# Nine-axis_Gyroscope_Module.net
KiCad netlist of a schematic drawn in Altium Designer
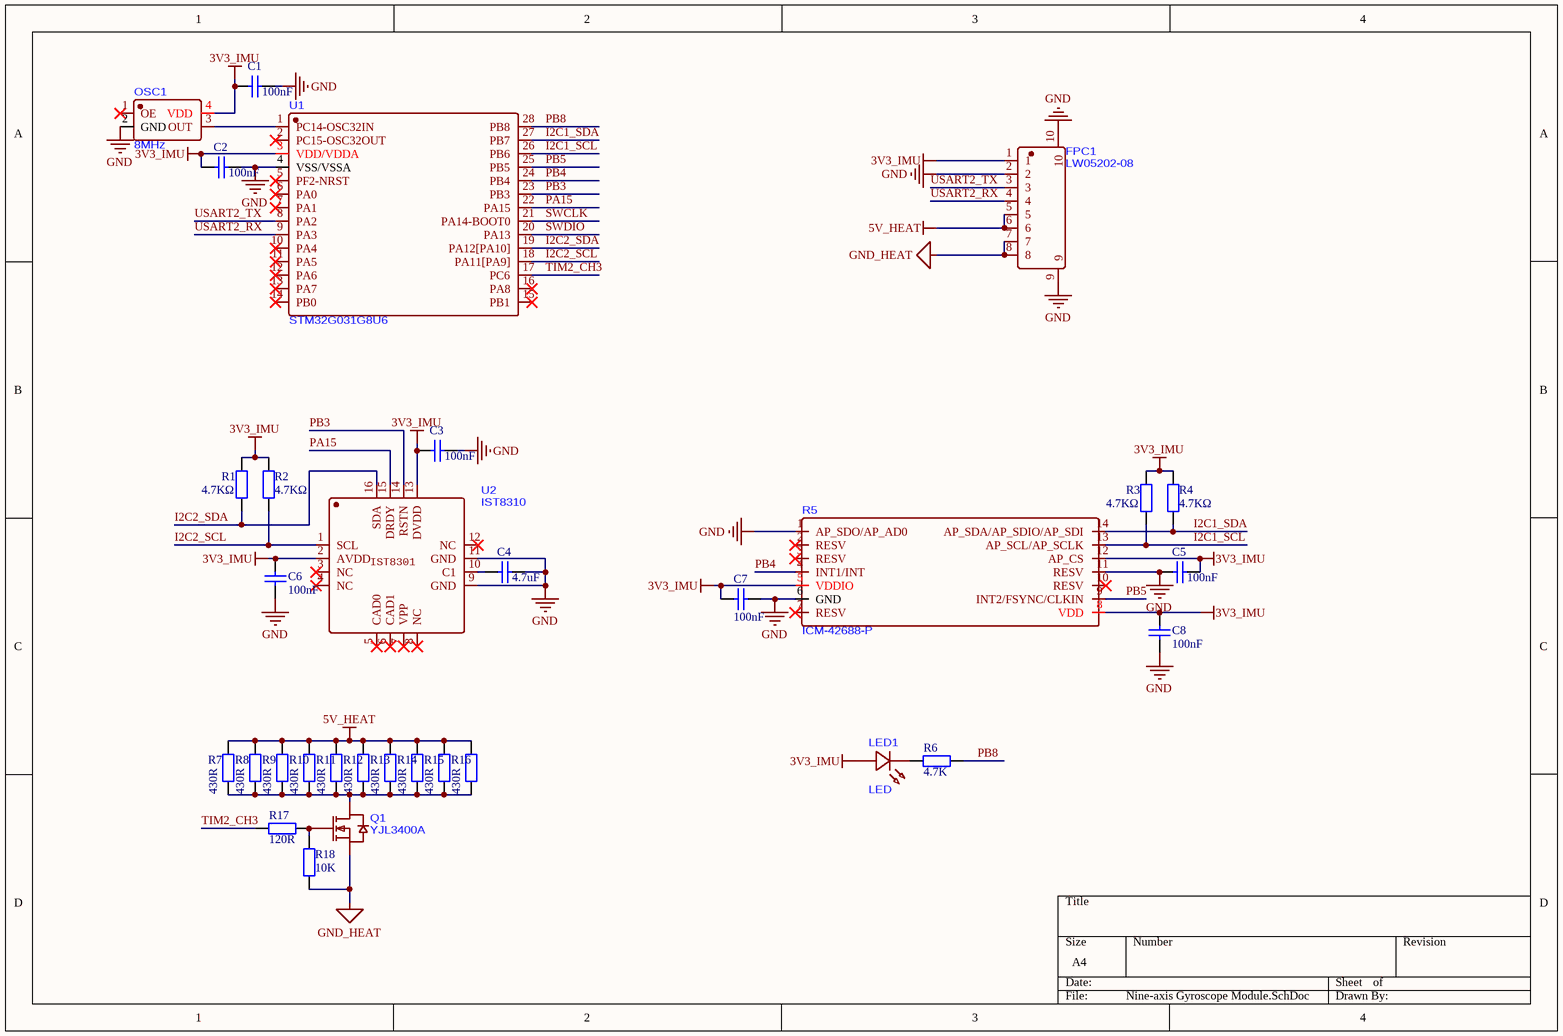
[diagram p0: Nine-axis Gyroscope Module.SchDoc]

(export (version "E")
  (design (tool "Eeschema 10.0.6"))
  (components
    (comp (ref "C1")
      (value "100nF")
      (footprint "0402_C")
      (description "贴片电容")
      (libsource (lib "Miscellaneous Devices LC") (part "0402 100nF (104) 10% 16V"))
    )
    (comp (ref "C2")
      (value "100nF")
      (footprint "0402_C")
      (description "贴片电容")
      (libsource (lib "Miscellaneous Devices LC") (part "0402 100nF (104) 10% 16V"))
    )
    (comp (ref "C3")
      (value "100nF")
      (footprint "0402_C")
      (description "贴片电容")
      (libsource (lib "Miscellaneous Devices LC") (part "0402 100nF (104) 10% 16V"))
    )
    (comp (ref "C4")
      (value "4.7uF")
      (footprint "0402_C")
      (description "贴片电容")
      (libsource (lib "Miscellaneous Devices LC") (part "0402 4.7uF (475) 20% 10V"))
    )
    (comp (ref "C5")
      (value "100nF")
      (footprint "0402_C")
      (description "贴片电容")
      (libsource (lib "Miscellaneous Devices LC") (part "0402 100nF (104) 10% 16V"))
    )
    (comp (ref "C6")
      (value "100nF")
      (footprint "0402_C")
      (description "贴片电容")
      (libsource (lib "Miscellaneous Devices LC") (part "0402 100nF (104) 10% 16V"))
    )
    (comp (ref "C7")
      (value "100nF")
      (footprint "0402_C")
      (description "贴片电容")
      (libsource (lib "Miscellaneous Devices LC") (part "0402 100nF (104) 10% 16V"))
    )
    (comp (ref "C8")
      (value "100nF")
      (footprint "0402_C")
      (description "贴片电容")
      (libsource (lib "Miscellaneous Devices LC") (part "0402 100nF (104) 10% 16V"))
    )
    (comp (ref "FPC1")
      (value "LW05202-08")
      (footprint "FPC-SMD_8P-P0.50_LW05202-08")
      (libsource (lib "VeryNB_H750") (part "LW05202-08"))
    )
    (comp (ref "LED1")
      (value "LED")
      (footprint "LED0402-RD")
      (libsource (lib "VeryNB_H750") (part "TJ-S1005CL4T5ALC3DW-A5"))
    )
    (comp (ref "OSC1")
      (value "8MHz")
      (footprint "OSC-SMD_4P-L2.0-W1.6-BL_ABRACON_AMPMAXXX")
      (libsource (lib "VeryNB_H750") (part "AMPMAFC-25.0000T"))
    )
    (comp (ref "Q1")
      (value "YJL3400A")
      (footprint "SOT-23-3_L2.9-W1.3-P1.90-LS2.4-BR")
      (libsource (lib "VeryNB_H750") (part "YJL3400A"))
    )
    (comp (ref "R1")
      (value "4.7KΩ")
      (footprint "0402_R")
      (description "贴片电阻")
      (libsource (lib "Miscellaneous Devices LC") (part "0402 4.7KΩ (4701) 1%"))
    )
    (comp (ref "R2")
      (value "4.7KΩ")
      (footprint "0402_R")
      (description "贴片电阻")
      (libsource (lib "Miscellaneous Devices LC") (part "0402 4.7KΩ (4701) 1%"))
    )
    (comp (ref "R3")
      (value "4.7KΩ")
      (footprint "0402_R")
      (description "贴片电阻")
      (libsource (lib "Miscellaneous Devices LC") (part "0402 4.7KΩ (4701) 1%"))
    )
    (comp (ref "R4")
      (value "4.7KΩ")
      (footprint "0402_R")
      (description "贴片电阻")
      (libsource (lib "Miscellaneous Devices LC") (part "0402 4.7KΩ (4701) 1%"))
    )
    (comp (ref "R5")
      (value "ICM-42688-P")
      (footprint "LGA-14_L3.0-W2.5-P0.50-TL")
      (libsource (lib "VeryNB_H750") (part "ICM-42688-P"))
    )
    (comp (ref "R6")
      (value "4.7K")
      (footprint "0402_R")
      (description "贴片电阻")
      (libsource (lib "") (part "0402 4.7KΩ (4701) 1%_3"))
    )
    (comp (ref "R7")
      (value "430R")
      (footprint "0402_R")
      (description "贴片电阻")
      (libsource (lib "Miscellaneous Devices LC") (part "0402 4.7KΩ (4701) 1%"))
    )
    (comp (ref "R8")
      (value "430R")
      (footprint "0402_R")
      (description "贴片电阻")
      (libsource (lib "Miscellaneous Devices LC") (part "0402 4.7KΩ (4701) 1%"))
    )
    (comp (ref "R9")
      (value "430R")
      (footprint "0402_R")
      (description "贴片电阻")
      (libsource (lib "Miscellaneous Devices LC") (part "0402 4.7KΩ (4701) 1%"))
    )
    (comp (ref "R10")
      (value "430R")
      (footprint "0402_R")
      (description "贴片电阻")
      (libsource (lib "Miscellaneous Devices LC") (part "0402 4.7KΩ (4701) 1%"))
    )
    (comp (ref "R11")
      (value "430R")
      (footprint "0402_R")
      (description "贴片电阻")
      (libsource (lib "Miscellaneous Devices LC") (part "0402 4.7KΩ (4701) 1%"))
    )
    (comp (ref "R12")
      (value "430R")
      (footprint "0402_R")
      (description "贴片电阻")
      (libsource (lib "Miscellaneous Devices LC") (part "0402 4.7KΩ (4701) 1%"))
    )
    (comp (ref "R13")
      (value "430R")
      (footprint "0402_R")
      (description "贴片电阻")
      (libsource (lib "Miscellaneous Devices LC") (part "0402 4.7KΩ (4701) 1%"))
    )
    (comp (ref "R14")
      (value "430R")
      (footprint "0402_R")
      (description "贴片电阻")
      (libsource (lib "Miscellaneous Devices LC") (part "0402 4.7KΩ (4701) 1%"))
    )
    (comp (ref "R15")
      (value "430R")
      (footprint "0402_R")
      (description "贴片电阻")
      (libsource (lib "Miscellaneous Devices LC") (part "0402 4.7KΩ (4701) 1%"))
    )
    (comp (ref "R16")
      (value "430R")
      (footprint "0402_R")
      (description "贴片电阻")
      (libsource (lib "Miscellaneous Devices LC") (part "0402 4.7KΩ (4701) 1%"))
    )
    (comp (ref "R17")
      (value "120R")
      (footprint "0402_R")
      (description "贴片电阻")
      (libsource (lib "") (part "0402 4.7KΩ (4701) 1%_1"))
    )
    (comp (ref "R18")
      (value "10K")
      (footprint "0402_R")
      (description "贴片电阻")
      (libsource (lib "") (part "0402 4.7KΩ (4701) 1%_2"))
    )
    (comp (ref "U1")
      (value "STM32G031G8U6")
      (footprint "UFQFPN-28_L4.0-W4.0-P0.50-BL")
      (libsource (lib "VeryNB_H750") (part "STM32G031G8U6"))
    )
    (comp (ref "U2")
      (value "IST8310")
      (footprint "LGA-16-3*3")
      (libsource (lib "VeryNB_H750") (part "IST8310"))
    )
  )
  (nets
    (net (code "1") (name "/I2C1_SCL") (class "Default")
      (node (ref "R3") (pin "1") (pinfunction "1_1") (pintype "passive"))
      (node (ref "R5") (pin "13") (pinfunction "AP_SCL/AP_SCLK_13") (pintype "passive"))
      (node (ref "U1") (pin "26") (pinfunction "PB6_26") (pintype "passive"))
    )
    (net (code "2") (name "/I2C1_SDA") (class "Default")
      (node (ref "R4") (pin "1") (pinfunction "1_1") (pintype "passive"))
      (node (ref "R5") (pin "14") (pinfunction "AP_SDA/AP_SDIO/AP_SDI_14") (pintype "passive"))
      (node (ref "U1") (pin "27") (pinfunction "PB7_27") (pintype "passive"))
    )
    (net (code "3") (name "/I2C2_SCL") (class "Default")
      (node (ref "R2") (pin "1") (pinfunction "1_1") (pintype "passive"))
      (node (ref "U1") (pin "18") (pinfunction "PA11[PA9]_18") (pintype "passive"))
      (node (ref "U2") (pin "1") (pinfunction "SCL_1") (pintype "passive"))
    )
    (net (code "4") (name "/I2C2_SDA") (class "Default")
      (node (ref "R1") (pin "1") (pinfunction "1_1") (pintype "passive"))
      (node (ref "U1") (pin "19") (pinfunction "PA12[PA10]_19") (pintype "passive"))
      (node (ref "U2") (pin "16") (pinfunction "SDA_16") (pintype "passive"))
    )
    (net (code "5") (name "/PA15") (class "Default")
      (node (ref "U1") (pin "22") (pinfunction "PA15_22") (pintype "passive"))
      (node (ref "U2") (pin "15") (pinfunction "DRDY_15") (pintype "passive"))
    )
    (net (code "6") (name "/PB3") (class "Default")
      (node (ref "U1") (pin "23") (pinfunction "PB3_23") (pintype "passive"))
      (node (ref "U2") (pin "14") (pinfunction "RSTN_14") (pintype "passive"))
    )
    (net (code "7") (name "/PB4") (class "Default")
      (node (ref "R5") (pin "4") (pinfunction "INT1/INT_4") (pintype "passive"))
      (node (ref "U1") (pin "24") (pinfunction "PB4_24") (pintype "passive"))
    )
    (net (code "8") (name "/PB5") (class "Default")
      (node (ref "R5") (pin "9") (pinfunction "INT2/FSYNC/CLKIN_9") (pintype "passive"))
      (node (ref "U1") (pin "25") (pinfunction "PB5_25") (pintype "passive"))
    )
    (net (code "9") (name "/PB8") (class "Default")
      (node (ref "R6") (pin "2") (pinfunction "2_2") (pintype "passive"))
      (node (ref "U1") (pin "28") (pinfunction "PB8_28") (pintype "passive"))
    )
    (net (code "10") (name "/SWCLK") (class "Default")
      (node (ref "U1") (pin "21") (pinfunction "PA14-BOOT0_21") (pintype "passive"))
    )
    (net (code "11") (name "/SWDIO") (class "Default")
      (node (ref "U1") (pin "20") (pinfunction "PA13_20") (pintype "passive"))
    )
    (net (code "12") (name "/TIM2_CH3") (class "Default")
      (node (ref "R17") (pin "2") (pinfunction "2_2") (pintype "passive"))
      (node (ref "U1") (pin "17") (pinfunction "PC6_17") (pintype "passive"))
    )
    (net (code "13") (name "/USART2_RX") (class "Default")
      (node (ref "FPC1") (pin "4") (pinfunction "4_4") (pintype "passive"))
      (node (ref "U1") (pin "9") (pinfunction "PA3_9") (pintype "passive"))
    )
    (net (code "14") (name "/USART2_TX") (class "Default")
      (node (ref "FPC1") (pin "3") (pinfunction "3_3") (pintype "passive"))
      (node (ref "U1") (pin "8") (pinfunction "PA2_8") (pintype "passive"))
    )
    (net (code "15") (name "3V3_IMU") (class "Default")
      (node (ref "C1") (pin "1") (pinfunction "1_1") (pintype "passive"))
      (node (ref "C2") (pin "1") (pinfunction "1_1") (pintype "passive"))
      (node (ref "C3") (pin "1") (pinfunction "1_1") (pintype "passive"))
      (node (ref "C5") (pin "2") (pinfunction "2_2") (pintype "passive"))
      (node (ref "C6") (pin "2") (pinfunction "2_2") (pintype "passive"))
      (node (ref "C7") (pin "1") (pinfunction "1_1") (pintype "passive"))
      (node (ref "C8") (pin "2") (pinfunction "2_2") (pintype "passive"))
      (node (ref "FPC1") (pin "1") (pinfunction "1_1") (pintype "passive"))
      (node (ref "LED1") (pin "2") (pinfunction "A_2") (pintype "passive"))
      (node (ref "OSC1") (pin "4") (pinfunction "VDD_4") (pintype "passive"))
      (node (ref "R1") (pin "2") (pinfunction "2_2") (pintype "passive"))
      (node (ref "R2") (pin "2") (pinfunction "2_2") (pintype "passive"))
      (node (ref "R3") (pin "2") (pinfunction "2_2") (pintype "passive"))
      (node (ref "R4") (pin "2") (pinfunction "2_2") (pintype "passive"))
      (node (ref "R5") (pin "12") (pinfunction "AP_CS_12") (pintype "passive"))
      (node (ref "R5") (pin "5") (pinfunction "VDDIO_5") (pintype "passive"))
      (node (ref "R5") (pin "8") (pinfunction "VDD_8") (pintype "passive"))
      (node (ref "U1") (pin "3") (pinfunction "VDD/VDDA_3") (pintype "passive"))
      (node (ref "U2") (pin "13") (pinfunction "DVDD_13") (pintype "passive"))
      (node (ref "U2") (pin "2") (pinfunction "AVDD_2") (pintype "passive"))
    )
    (net (code "16") (name "5V_HEAT") (class "Default")
      (node (ref "FPC1") (pin "5") (pinfunction "5_5") (pintype "passive"))
      (node (ref "FPC1") (pin "6") (pinfunction "6_6") (pintype "passive"))
      (node (ref "R10") (pin "2") (pinfunction "2_2") (pintype "passive"))
      (node (ref "R11") (pin "2") (pinfunction "2_2") (pintype "passive"))
      (node (ref "R12") (pin "2") (pinfunction "2_2") (pintype "passive"))
      (node (ref "R13") (pin "2") (pinfunction "2_2") (pintype "passive"))
      (node (ref "R14") (pin "2") (pinfunction "2_2") (pintype "passive"))
      (node (ref "R15") (pin "2") (pinfunction "2_2") (pintype "passive"))
      (node (ref "R16") (pin "2") (pinfunction "2_2") (pintype "passive"))
      (node (ref "R7") (pin "2") (pinfunction "2_2") (pintype "passive"))
      (node (ref "R8") (pin "2") (pinfunction "2_2") (pintype "passive"))
      (node (ref "R9") (pin "2") (pinfunction "2_2") (pintype "passive"))
    )
    (net (code "17") (name "GND") (class "Default")
      (node (ref "C1") (pin "2") (pinfunction "2_2") (pintype "passive"))
      (node (ref "C2") (pin "2") (pinfunction "2_2") (pintype "passive"))
      (node (ref "C3") (pin "2") (pinfunction "2_2") (pintype "passive"))
      (node (ref "C4") (pin "2") (pinfunction "2_2") (pintype "passive"))
      (node (ref "C5") (pin "1") (pinfunction "1_1") (pintype "passive"))
      (node (ref "C6") (pin "1") (pinfunction "1_1") (pintype "passive"))
      (node (ref "C7") (pin "2") (pinfunction "2_2") (pintype "passive"))
      (node (ref "C8") (pin "1") (pinfunction "1_1") (pintype "passive"))
      (node (ref "FPC1") (pin "10") (pinfunction "10_10") (pintype "passive"))
      (node (ref "FPC1") (pin "2") (pinfunction "2_2") (pintype "passive"))
      (node (ref "FPC1") (pin "9") (pinfunction "9_9") (pintype "passive"))
      (node (ref "OSC1") (pin "2") (pinfunction "GND_2") (pintype "passive"))
      (node (ref "R5") (pin "1") (pinfunction "AP_SDO/AP_AD0_1") (pintype "passive"))
      (node (ref "R5") (pin "11") (pinfunction "RESV_11") (pintype "passive"))
      (node (ref "R5") (pin "6") (pinfunction "GND_6") (pintype "passive"))
      (node (ref "U1") (pin "4") (pinfunction "VSS/VSSA_4") (pintype "passive"))
      (node (ref "U2") (pin "11") (pinfunction "GND_11") (pintype "passive"))
      (node (ref "U2") (pin "9") (pinfunction "GND_9") (pintype "passive"))
    )
    (net (code "18") (name "GND_HEAT") (class "Default")
      (node (ref "FPC1") (pin "7") (pinfunction "7_7") (pintype "passive"))
      (node (ref "FPC1") (pin "8") (pinfunction "8_8") (pintype "passive"))
      (node (ref "Q1") (pin "2") (pinfunction "S_2") (pintype "passive"))
      (node (ref "R18") (pin "2") (pinfunction "2_2") (pintype "passive"))
    )
    (net (code "19") (name "Net-(LED1-K)") (class "Default")
      (node (ref "LED1") (pin "1") (pinfunction "K_1") (pintype "passive"))
      (node (ref "R6") (pin "1") (pinfunction "1_1") (pintype "passive"))
    )
    (net (code "20") (name "Net-(OSC1-OUT)") (class "Default")
      (node (ref "OSC1") (pin "3") (pinfunction "OUT_3") (pintype "passive"))
      (node (ref "U1") (pin "1") (pinfunction "PC14-OSC32IN_1") (pintype "passive"))
    )
    (net (code "21") (name "Net-(Q1-D)") (class "Default")
      (node (ref "Q1") (pin "3") (pinfunction "D_3") (pintype "passive"))
      (node (ref "R10") (pin "1") (pinfunction "1_1") (pintype "passive"))
      (node (ref "R11") (pin "1") (pinfunction "1_1") (pintype "passive"))
      (node (ref "R12") (pin "1") (pinfunction "1_1") (pintype "passive"))
      (node (ref "R13") (pin "1") (pinfunction "1_1") (pintype "passive"))
      (node (ref "R14") (pin "1") (pinfunction "1_1") (pintype "passive"))
      (node (ref "R15") (pin "1") (pinfunction "1_1") (pintype "passive"))
      (node (ref "R16") (pin "1") (pinfunction "1_1") (pintype "passive"))
      (node (ref "R7") (pin "1") (pinfunction "1_1") (pintype "passive"))
      (node (ref "R8") (pin "1") (pinfunction "1_1") (pintype "passive"))
      (node (ref "R9") (pin "1") (pinfunction "1_1") (pintype "passive"))
    )
    (net (code "22") (name "Net-(Q1-G)") (class "Default")
      (node (ref "Q1") (pin "1") (pinfunction "G_1") (pintype "passive"))
      (node (ref "R17") (pin "1") (pinfunction "1_1") (pintype "passive"))
      (node (ref "R18") (pin "1") (pinfunction "1_1") (pintype "passive"))
    )
    (net (code "23") (name "Net-(U2-C1)") (class "Default")
      (node (ref "C4") (pin "1") (pinfunction "1_1") (pintype "passive"))
      (node (ref "U2") (pin "10") (pinfunction "C1_10") (pintype "passive"))
    )
    (net (code "24") (name "unconnected-(OSC1-OE-Pad1)") (class "Default")
      (node (ref "OSC1") (pin "1") (pinfunction "OE_1") (pintype "passive+no_connect"))
    )
    (net (code "25") (name "unconnected-(R5-RESV-Pad2)") (class "Default")
      (node (ref "R5") (pin "2") (pinfunction "RESV_2") (pintype "passive+no_connect"))
    )
    (net (code "26") (name "unconnected-(R5-RESV-Pad3)") (class "Default")
      (node (ref "R5") (pin "3") (pinfunction "RESV_3") (pintype "passive+no_connect"))
    )
    (net (code "27") (name "unconnected-(R5-RESV-Pad7)") (class "Default")
      (node (ref "R5") (pin "7") (pinfunction "RESV_7") (pintype "passive+no_connect"))
    )
    (net (code "28") (name "unconnected-(R5-RESV-Pad10)") (class "Default")
      (node (ref "R5") (pin "10") (pinfunction "RESV_10") (pintype "passive+no_connect"))
    )
    (net (code "29") (name "unconnected-(U1-PA0-Pad6)") (class "Default")
      (node (ref "U1") (pin "6") (pinfunction "PA0_6") (pintype "passive+no_connect"))
    )
    (net (code "30") (name "unconnected-(U1-PA1-Pad7)") (class "Default")
      (node (ref "U1") (pin "7") (pinfunction "PA1_7") (pintype "passive+no_connect"))
    )
    (net (code "31") (name "unconnected-(U1-PA4-Pad10)") (class "Default")
      (node (ref "U1") (pin "10") (pinfunction "PA4_10") (pintype "passive+no_connect"))
    )
    (net (code "32") (name "unconnected-(U1-PA5-Pad11)") (class "Default")
      (node (ref "U1") (pin "11") (pinfunction "PA5_11") (pintype "passive+no_connect"))
    )
    (net (code "33") (name "unconnected-(U1-PA6-Pad12)") (class "Default")
      (node (ref "U1") (pin "12") (pinfunction "PA6_12") (pintype "passive+no_connect"))
    )
    (net (code "34") (name "unconnected-(U1-PA7-Pad13)") (class "Default")
      (node (ref "U1") (pin "13") (pinfunction "PA7_13") (pintype "passive+no_connect"))
    )
    (net (code "35") (name "unconnected-(U1-PA8-Pad16)") (class "Default")
      (node (ref "U1") (pin "16") (pinfunction "PA8_16") (pintype "passive+no_connect"))
    )
    (net (code "36") (name "unconnected-(U1-PB0-Pad14)") (class "Default")
      (node (ref "U1") (pin "14") (pinfunction "PB0_14") (pintype "passive+no_connect"))
    )
    (net (code "37") (name "unconnected-(U1-PB1-Pad15)") (class "Default")
      (node (ref "U1") (pin "15") (pinfunction "PB1_15") (pintype "passive+no_connect"))
    )
    (net (code "38") (name "unconnected-(U1-PC15-OSC32OUT-Pad2)") (class "Default")
      (node (ref "U1") (pin "2") (pinfunction "PC15-OSC32OUT_2") (pintype "passive+no_connect"))
    )
    (net (code "39") (name "unconnected-(U1-PF2-NRST-Pad5)") (class "Default")
      (node (ref "U1") (pin "5") (pinfunction "PF2-NRST_5") (pintype "passive+no_connect"))
    )
    (net (code "40") (name "unconnected-(U2-CAD0-Pad5)") (class "Default")
      (node (ref "U2") (pin "5") (pinfunction "CAD0_5") (pintype "passive+no_connect"))
    )
    (net (code "41") (name "unconnected-(U2-CAD1-Pad6)") (class "Default")
      (node (ref "U2") (pin "6") (pinfunction "CAD1_6") (pintype "passive+no_connect"))
    )
    (net (code "42") (name "unconnected-(U2-NC-Pad3)") (class "Default")
      (node (ref "U2") (pin "3") (pinfunction "NC_3") (pintype "passive+no_connect"))
    )
    (net (code "43") (name "unconnected-(U2-NC-Pad4)") (class "Default")
      (node (ref "U2") (pin "4") (pinfunction "NC_4") (pintype "passive+no_connect"))
    )
    (net (code "44") (name "unconnected-(U2-NC-Pad8)") (class "Default")
      (node (ref "U2") (pin "8") (pinfunction "NC_8") (pintype "passive+no_connect"))
    )
    (net (code "45") (name "unconnected-(U2-NC-Pad12)") (class "Default")
      (node (ref "U2") (pin "12") (pinfunction "NC_12") (pintype "passive+no_connect"))
    )
    (net (code "46") (name "unconnected-(U2-VPP-Pad7)") (class "Default")
      (node (ref "U2") (pin "7") (pinfunction "VPP_7") (pintype "passive+no_connect"))
    )
  )
)
